# blink1mk3_usbc3535A.net
KiCad netlist of a schematic drawn in EAGLE
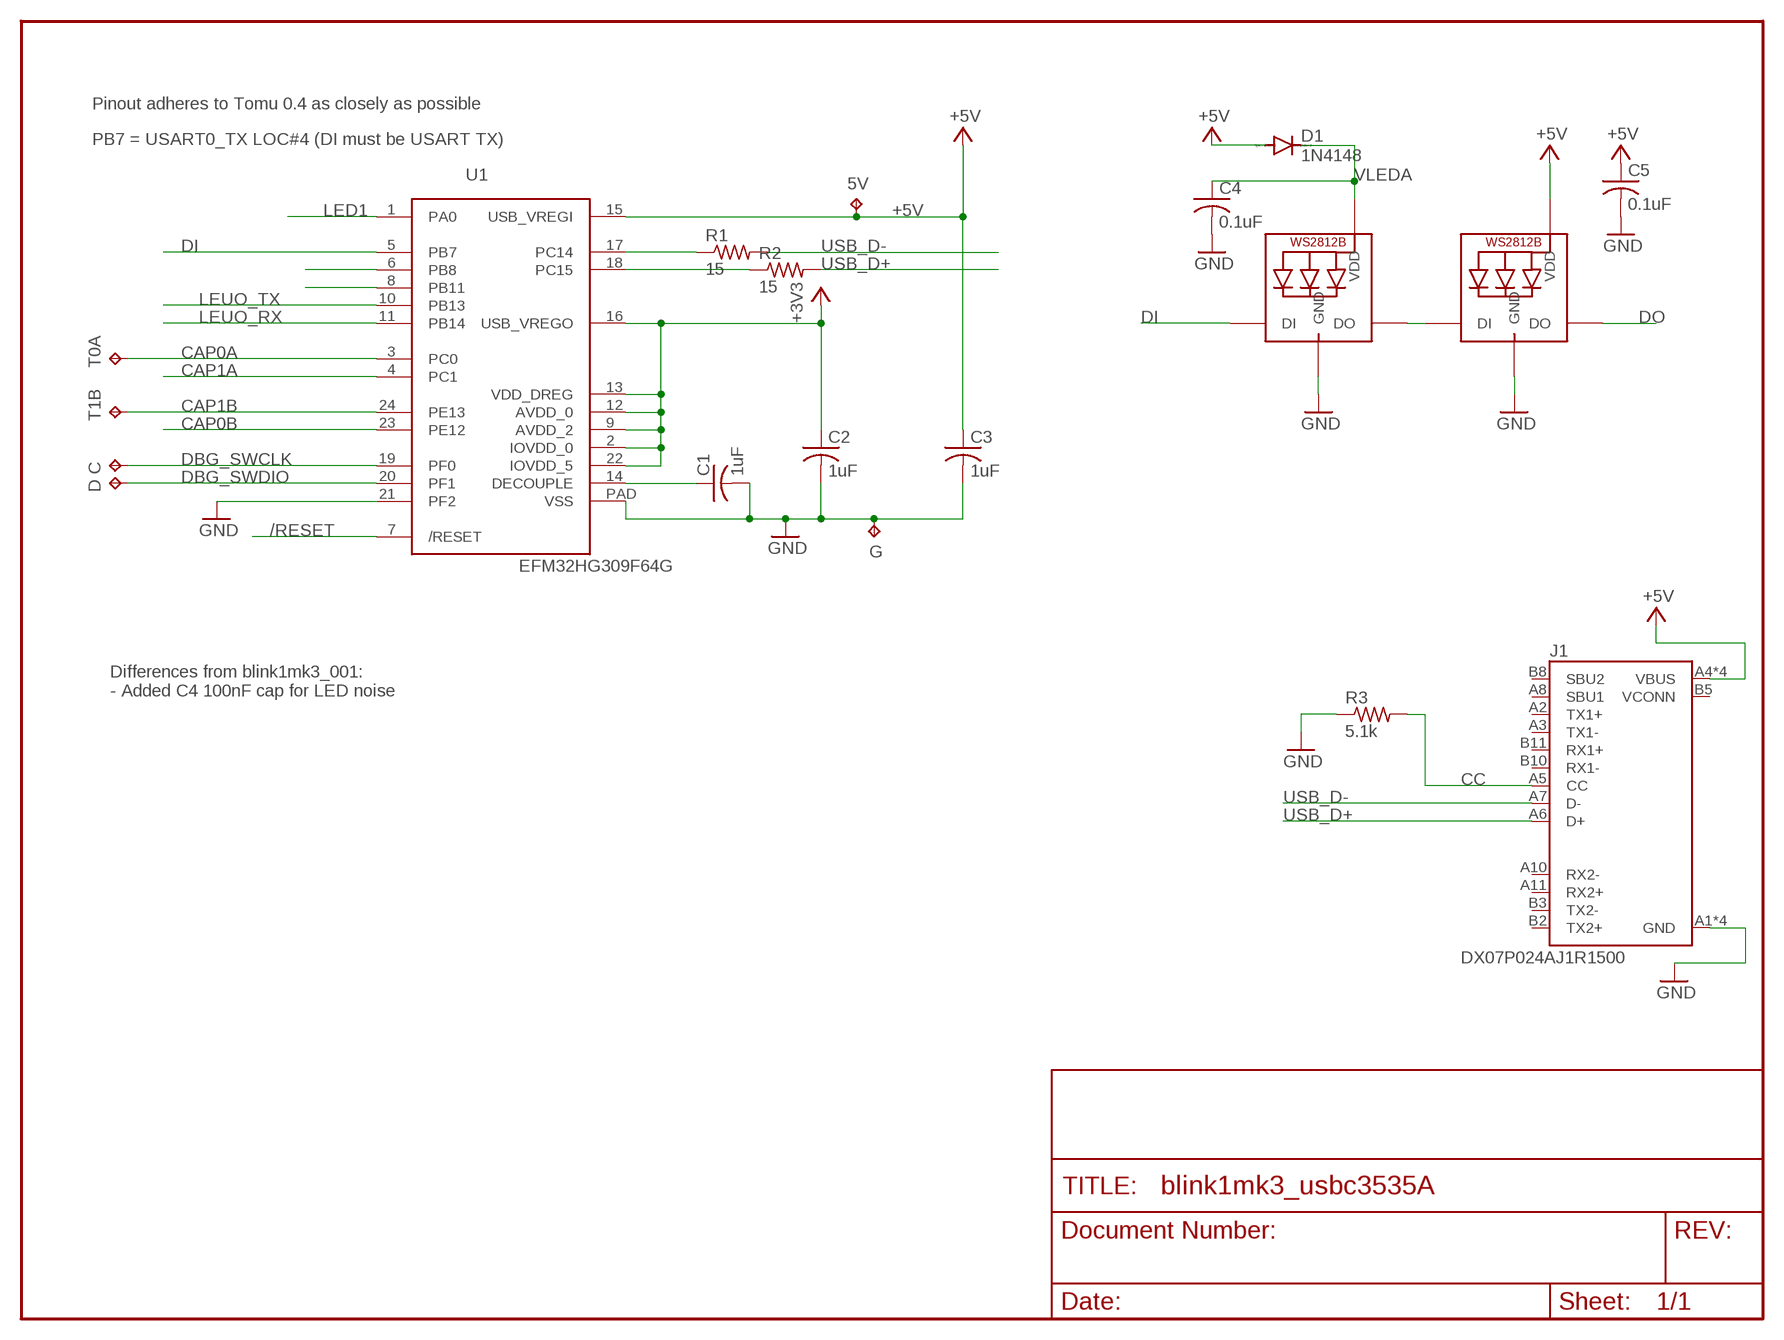
[diagram p0: schematic, sheet 1]

(export (version "E")
  (design (tool "Eeschema 10.0.6"))
  (components
    (comp (ref "5V")
      (value "TPTP10R")
      (footprint "eagle-import:TP10R")
      (libsource (lib "eagle-import") (part "TPTP10R"))
    )
    (comp (ref "C")
      (value "TPTP10R")
      (footprint "eagle-import:TP10R")
      (libsource (lib "eagle-import") (part "TPTP10R"))
    )
    (comp (ref "C1")
      (value "1uF")
      (footprint "eagle-import:C0402")
      (libsource (lib "eagle-import") (part "C-USC0402"))
    )
    (comp (ref "C2")
      (value "1uF")
      (footprint "eagle-import:C0402")
      (libsource (lib "eagle-import") (part "C-USC0402"))
    )
    (comp (ref "C3")
      (value "1uF")
      (footprint "eagle-import:C0402")
      (libsource (lib "eagle-import") (part "C-USC0402"))
    )
    (comp (ref "C4")
      (value "0.1uF")
      (footprint "eagle-import:C0402")
      (libsource (lib "eagle-import") (part "C-USC0402"))
    )
    (comp (ref "C5")
      (value "0.1uF")
      (footprint "eagle-import:C0402")
      (libsource (lib "eagle-import") (part "C-USC0402"))
    )
    (comp (ref "D")
      (value "TPTP10R")
      (footprint "eagle-import:TP10R")
      (libsource (lib "eagle-import") (part "TPTP10R"))
    )
    (comp (ref "D1")
      (value "1N4148")
      (footprint "eagle-import:SOD523")
      (libsource (lib "eagle-import") (part "DIODE-SOD523"))
    )
    (comp (ref "G")
      (value "TPTP10R")
      (footprint "eagle-import:TP10R")
      (libsource (lib "eagle-import") (part "TPTP10R"))
    )
    (comp (ref "J1")
      (value "DX07P024AJ1R1500")
      (footprint "eagle-import:JAE_DX07P024AJ1R1500")
      (fields (field (name "DIGI-KEY_PART_NUMBER") "670-2868-1-ND") (field (name "MF") "JAE Electronics"))
      (libsource (lib "eagle-import") (part "DX07P024AJ1R1500"))
    )
    (comp (ref "LED1")
      (value "WS2812B3535")
      (footprint "eagle-import:LED3535")
      (libsource (lib "eagle-import") (part "todstuff_1731349_WS2812B3535"))
    )
    (comp (ref "LED2")
      (value "SK6812MINI")
      (footprint "eagle-import:LED3535")
      (libsource (lib "eagle-import") (part "WS2812B3535"))
    )
    (comp (ref "R1")
      (value "15")
      (footprint "eagle-import:R0402")
      (libsource (lib "eagle-import") (part "R-US_R0402"))
    )
    (comp (ref "R2")
      (value "15")
      (footprint "eagle-import:R0402")
      (libsource (lib "eagle-import") (part "R-US_R0402"))
    )
    (comp (ref "R3")
      (value "5.1k")
      (footprint "eagle-import:R0402")
      (libsource (lib "eagle-import") (part "R-US_R0402"))
    )
    (comp (ref "T0A")
      (value "TPTP10R")
      (footprint "eagle-import:TP10R")
      (libsource (lib "eagle-import") (part "TPTP10R"))
    )
    (comp (ref "T1B")
      (value "TPTP10R")
      (footprint "eagle-import:TP10R")
      (libsource (lib "eagle-import") (part "TPTP10R"))
    )
    (comp (ref "U1")
      (value "EFM32HG309F64G")
      (footprint "eagle-import:QFN24PAD")
      (libsource (lib "eagle-import") (part "EFM32HG309F64G"))
    )
  )
  (nets
    (net (code "1") (name "+3V3") (class "Default")
      (node (ref "C2") (pin "1") (pinfunction "1_1") (pintype "passive"))
      (node (ref "U1") (pin "12") (pinfunction "AVDD_0_12") (pintype "bidirectional"))
      (node (ref "U1") (pin "13") (pinfunction "VDD_DREG_13") (pintype "bidirectional"))
      (node (ref "U1") (pin "16") (pinfunction "USB_VREGO_16") (pintype "bidirectional"))
      (node (ref "U1") (pin "2") (pinfunction "IOVDD_0_2") (pintype "bidirectional"))
      (node (ref "U1") (pin "22") (pinfunction "IOVDD_5_22") (pintype "bidirectional"))
      (node (ref "U1") (pin "9") (pinfunction "AVDD_2_9") (pintype "bidirectional"))
    )
    (net (code "2") (name "+5V") (class "Default")
      (node (ref "5V") (pin "TP") (pinfunction "TP_TP") (pintype "input"))
      (node (ref "C3") (pin "1") (pinfunction "1_1") (pintype "passive"))
      (node (ref "C5") (pin "1") (pinfunction "1_1") (pintype "passive"))
      (node (ref "D1") (pin "A") (pinfunction "A_A") (pintype "passive"))
      (node (ref "J1") (pin "A4") (pinfunction "VBUS_A4") (pintype "power_in"))
      (node (ref "J1") (pin "A9") (pinfunction "VBUS_A9") (pintype "power_in"))
      (node (ref "J1") (pin "B4") (pinfunction "VBUS_B4") (pintype "power_in"))
      (node (ref "J1") (pin "B9") (pinfunction "VBUS_B9") (pintype "power_in"))
      (node (ref "LED2") (pin "2") (pinfunction "VDD_2") (pintype "power_in"))
      (node (ref "U1") (pin "15") (pinfunction "USB_VREGI_15") (pintype "bidirectional"))
    )
    (net (code "3") (name "/CAP0A") (class "Default")
      (node (ref "T0A") (pin "TP") (pinfunction "TP_TP") (pintype "input"))
      (node (ref "U1") (pin "3") (pinfunction "PC0_3") (pintype "bidirectional"))
    )
    (net (code "4") (name "/CAP0B") (class "Default")
      (node (ref "U1") (pin "23") (pinfunction "PE12_23") (pintype "bidirectional"))
    )
    (net (code "5") (name "/CAP1A") (class "Default")
      (node (ref "U1") (pin "4") (pinfunction "PC1_4") (pintype "bidirectional"))
    )
    (net (code "6") (name "/CAP1B") (class "Default")
      (node (ref "T1B") (pin "TP") (pinfunction "TP_TP") (pintype "input"))
      (node (ref "U1") (pin "24") (pinfunction "PE13_24") (pintype "bidirectional"))
    )
    (net (code "7") (name "/CC") (class "Default")
      (node (ref "J1") (pin "A5") (pinfunction "CC_A5") (pintype "bidirectional"))
      (node (ref "R3") (pin "2") (pinfunction "2_2") (pintype "passive"))
    )
    (net (code "8") (name "/DBG_SWCLK") (class "Default")
      (node (ref "C") (pin "TP") (pinfunction "TP_TP") (pintype "input"))
      (node (ref "U1") (pin "19") (pinfunction "PF0_19") (pintype "bidirectional"))
    )
    (net (code "9") (name "/DBG_SWDIO") (class "Default")
      (node (ref "D") (pin "TP") (pinfunction "TP_TP") (pintype "input"))
      (node (ref "U1") (pin "20") (pinfunction "PF1_20") (pintype "bidirectional"))
    )
    (net (code "10") (name "/DI") (class "Default")
      (node (ref "LED1") (pin "1") (pinfunction "DI_1") (pintype "input"))
      (node (ref "U1") (pin "5") (pinfunction "PB7_5") (pintype "bidirectional"))
    )
    (net (code "11") (name "/DO") (class "Default")
      (node (ref "LED2") (pin "3") (pinfunction "DO_3") (pintype "output"))
    )
    (net (code "12") (name "/LED1") (class "Default")
      (node (ref "U1") (pin "1") (pinfunction "PA0_1") (pintype "bidirectional"))
    )
    (net (code "13") (name "/LEUO_RX") (class "Default")
      (node (ref "U1") (pin "11") (pinfunction "PB14_11") (pintype "bidirectional"))
    )
    (net (code "14") (name "/LEUO_TX") (class "Default")
      (node (ref "U1") (pin "10") (pinfunction "PB13_10") (pintype "bidirectional"))
    )
    (net (code "15") (name "/USB_D+") (class "Default")
      (node (ref "J1") (pin "A6") (pinfunction "D+_A6") (pintype "bidirectional"))
      (node (ref "R2") (pin "2") (pinfunction "2_2") (pintype "passive"))
    )
    (net (code "16") (name "/USB_D-") (class "Default")
      (node (ref "J1") (pin "A7") (pinfunction "D-_A7") (pintype "bidirectional"))
      (node (ref "R1") (pin "2") (pinfunction "2_2") (pintype "passive"))
    )
    (net (code "17") (name "/VCONN") (class "Default")
      (node (ref "J1") (pin "B5") (pinfunction "VCONN_B5") (pintype "power_in"))
    )
    (net (code "18") (name "/VLEDA") (class "Default")
      (node (ref "C4") (pin "1") (pinfunction "1_1") (pintype "passive"))
      (node (ref "D1") (pin "C") (pinfunction "C_C") (pintype "passive"))
      (node (ref "LED1") (pin "2") (pinfunction "VDD_2") (pintype "power_in"))
    )
    (net (code "19") (name "/{slash}RESET") (class "Default")
      (node (ref "U1") (pin "7") (pinfunction "/RESET_7") (pintype "bidirectional"))
    )
    (net (code "20") (name "GND") (class "Default")
      (node (ref "C1") (pin "2") (pinfunction "2_2") (pintype "passive"))
      (node (ref "C2") (pin "2") (pinfunction "2_2") (pintype "passive"))
      (node (ref "C3") (pin "2") (pinfunction "2_2") (pintype "passive"))
      (node (ref "C4") (pin "2") (pinfunction "2_2") (pintype "passive"))
      (node (ref "C5") (pin "2") (pinfunction "2_2") (pintype "passive"))
      (node (ref "G") (pin "TP") (pinfunction "TP_TP") (pintype "input"))
      (node (ref "J1") (pin "A1") (pinfunction "GND_A1") (pintype "power_in"))
      (node (ref "J1") (pin "A12") (pinfunction "GND_A12") (pintype "power_in"))
      (node (ref "J1") (pin "B1") (pinfunction "GND_B1") (pintype "power_in"))
      (node (ref "J1") (pin "B12") (pinfunction "GND_B12") (pintype "power_in"))
      (node (ref "LED1") (pin "4") (pinfunction "GND_4") (pintype "power_in"))
      (node (ref "LED2") (pin "4") (pinfunction "GND_4") (pintype "power_in"))
      (node (ref "R3") (pin "1") (pinfunction "1_1") (pintype "passive"))
      (node (ref "U1") (pin "21") (pinfunction "PF2_21") (pintype "bidirectional"))
      (node (ref "U1") (pin "PAD") (pinfunction "VSS_PAD") (pintype "bidirectional"))
    )
    (net (code "21") (name "Net-(LED1-DO)") (class "Default")
      (node (ref "LED1") (pin "3") (pinfunction "DO_3") (pintype "output"))
      (node (ref "LED2") (pin "1") (pinfunction "DI_1") (pintype "input"))
    )
    (net (code "22") (name "Net-(U1-DECOUPLE)") (class "Default")
      (node (ref "C1") (pin "1") (pinfunction "1_1") (pintype "passive"))
      (node (ref "U1") (pin "14") (pinfunction "DECOUPLE_14") (pintype "bidirectional"))
    )
    (net (code "23") (name "Net-(U1-PC14)") (class "Default")
      (node (ref "R1") (pin "1") (pinfunction "1_1") (pintype "passive"))
      (node (ref "U1") (pin "17") (pinfunction "PC14_17") (pintype "bidirectional"))
    )
    (net (code "24") (name "Net-(U1-PC15)") (class "Default")
      (node (ref "R2") (pin "1") (pinfunction "1_1") (pintype "passive"))
      (node (ref "U1") (pin "18") (pinfunction "PC15_18") (pintype "bidirectional"))
    )
    (net (code "25") (name "unconnected-(J1-RX1+-PadB11)") (class "Default")
      (node (ref "J1") (pin "B11") (pinfunction "RX1+_B11") (pintype "bidirectional"))
    )
    (net (code "26") (name "unconnected-(J1-RX1--PadB10)") (class "Default")
      (node (ref "J1") (pin "B10") (pinfunction "RX1-_B10") (pintype "bidirectional"))
    )
    (net (code "27") (name "unconnected-(J1-RX2+-PadA11)") (class "Default")
      (node (ref "J1") (pin "A11") (pinfunction "RX2+_A11") (pintype "bidirectional"))
    )
    (net (code "28") (name "unconnected-(J1-RX2--PadA10)") (class "Default")
      (node (ref "J1") (pin "A10") (pinfunction "RX2-_A10") (pintype "bidirectional"))
    )
    (net (code "29") (name "unconnected-(J1-SBU1-PadA8)") (class "Default")
      (node (ref "J1") (pin "A8") (pinfunction "SBU1_A8") (pintype "bidirectional"))
    )
    (net (code "30") (name "unconnected-(J1-SBU2-PadB8)") (class "Default")
      (node (ref "J1") (pin "B8") (pinfunction "SBU2_B8") (pintype "bidirectional"))
    )
    (net (code "31") (name "unconnected-(J1-TX1+-PadA2)") (class "Default")
      (node (ref "J1") (pin "A2") (pinfunction "TX1+_A2") (pintype "bidirectional"))
    )
    (net (code "32") (name "unconnected-(J1-TX1--PadA3)") (class "Default")
      (node (ref "J1") (pin "A3") (pinfunction "TX1-_A3") (pintype "bidirectional"))
    )
    (net (code "33") (name "unconnected-(J1-TX2+-PadB2)") (class "Default")
      (node (ref "J1") (pin "B2") (pinfunction "TX2+_B2") (pintype "bidirectional"))
    )
    (net (code "34") (name "unconnected-(J1-TX2--PadB3)") (class "Default")
      (node (ref "J1") (pin "B3") (pinfunction "TX2-_B3") (pintype "bidirectional"))
    )
    (net (code "35") (name "unconnected-(U1-PB8-Pad6)") (class "Default")
      (node (ref "U1") (pin "6") (pinfunction "PB8_6") (pintype "bidirectional"))
    )
    (net (code "36") (name "unconnected-(U1-PB11-Pad8)") (class "Default")
      (node (ref "U1") (pin "8") (pinfunction "PB11_8") (pintype "bidirectional"))
    )
  )
)
